# PCA_0005_FULL_CB_Power_REV_B.net
KiCad netlist of a schematic drawn in Altium Designer
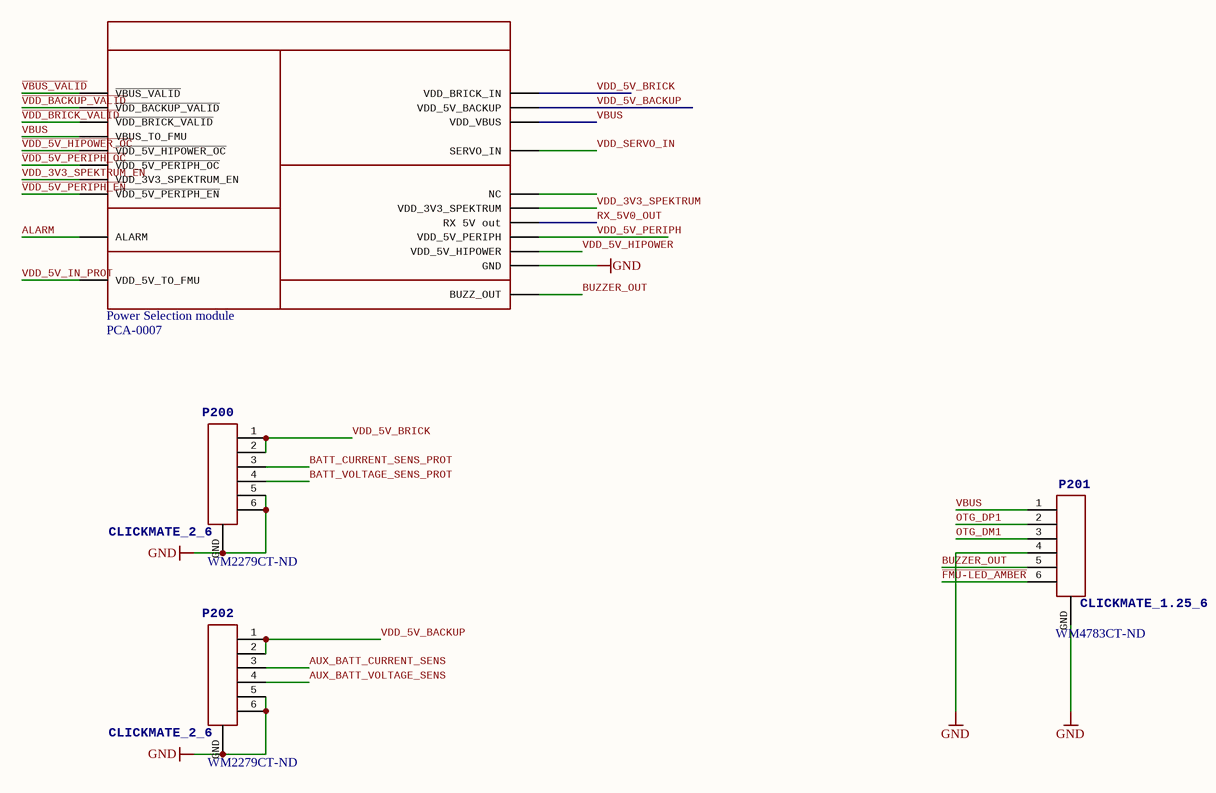
[diagram p0: PCA_0005_FULL_CB_Power_REV_B.SchDoc]

(export (version "E")
  (design (tool "Eeschema 10.0.6"))
  (components
    (comp (ref "P200")
      (value "CLICKMATE_2_6")
      (footprint "CLICKMATE_V6_2MM")
      (description "Connector, Header, 6Pos, 2.54MM, Vert, THT, Au")
      (fields (field (name "SUPPLIER PART NUMBER 1") "WM2279CT-ND") (field (name "3DR_PARTNO") "PRT0445"))
      (libsource (lib "PCA_0005_FULL_CB_REV_A") (part "CLICKMATE_2_6"))
    )
    (comp (ref "P201")
      (value "CLICKMATE_1.25_6")
      (footprint "CLICKMATE_V6")
      (description "Connector, Rcpt, 6Pos, 1.25MM, W/B, VERT, SMD, Tin")
      (fields (field (name "SUPPLIER PART NUMBER 1") "WM4783CT-ND") (field (name "3DR_PARTNO") "PRT0439"))
      (libsource (lib "PCA_0005_FULL_CB_REV_A") (part "CLICKMATE_1.25_6"))
    )
    (comp (ref "P202")
      (value "CLICKMATE_2_6")
      (footprint "CLICKMATE_V6_2MM")
      (description "Connector, Header, 6Pos, 2.54MM, Vert, THT, Au")
      (fields (field (name "SUPPLIER PART NUMBER 1") "WM2279CT-ND") (field (name "3DR_PARTNO") "PRT0445"))
      (libsource (lib "PCA_0005_FULL_CB_REV_A") (part "CLICKMATE_2_6"))
    )
    (comp (ref "PSM200")
      (value "Power Selection module")
      (footprint "PSM")
      (description "PCA, PSM, PX4, Assembly")
      (fields (field (name "SUPPLIER PART NUMBER 1") "PCA-0007") (field (name "3DR_PARTNO") "PCA0007"))
      (libsource (lib "PCA_0005_FULL_CB_REV_A") (part "PSMPSM"))
    )
  )
  (nets
    (net (code "1") (name "/ALARM") (class "Default")
      (node (ref "PSM200") (pin "ALARM") (pinfunction "ALARM_ALARM") (pintype "passive"))
    )
    (net (code "2") (name "/AUX_BATT_CURRENT_SENS") (class "Default")
      (node (ref "P202") (pin "3") (pinfunction "3_3") (pintype "passive"))
    )
    (net (code "3") (name "/AUX_BATT_VOLTAGE_SENS") (class "Default")
      (node (ref "P202") (pin "4") (pinfunction "4_4") (pintype "passive"))
    )
    (net (code "4") (name "/BATT_CURRENT_SENS_PROT") (class "Default")
      (node (ref "P200") (pin "3") (pinfunction "3_3") (pintype "passive"))
    )
    (net (code "5") (name "/BATT_VOLTAGE_SENS_PROT") (class "Default")
      (node (ref "P200") (pin "4") (pinfunction "4_4") (pintype "passive"))
    )
    (net (code "6") (name "/BUZZER_OUT") (class "Default")
      (node (ref "P201") (pin "5") (pinfunction "5_5") (pintype "passive"))
      (node (ref "PSM200") (pin "BUZZER_OUT") (pinfunction "BUZZ_OUT_BUZZER_OUT") (pintype "passive"))
    )
    (net (code "7") (name "/OTG_DM1") (class "Default")
      (node (ref "P201") (pin "3") (pinfunction "3_3") (pintype "passive"))
    )
    (net (code "8") (name "/OTG_DP1") (class "Default")
      (node (ref "P201") (pin "2") (pinfunction "2_2") (pintype "passive"))
    )
    (net (code "9") (name "/RX_5V0_OUT") (class "Default")
      (node (ref "PSM200") (pin "RX") (pinfunction "RX_5V_out_RX") (pintype "passive"))
    )
    (net (code "10") (name "/VBUS") (class "Default")
      (node (ref "P201") (pin "1") (pinfunction "1_1") (pintype "passive"))
      (node (ref "PSM200") (pin "VBUS") (pinfunction "VBUS_TO_FMU_VBUS") (pintype "passive"))
      (node (ref "PSM200") (pin "VDD_VBUS") (pinfunction "VDD_VBUS_VDD_VBUS") (pintype "passive"))
    )
    (net (code "11") (name "/VDD_3V3_SPEKTRUM") (class "Default")
      (node (ref "PSM200") (pin "SPEK") (pinfunction "VDD_3V3_SPEKTRUM_SPEK") (pintype "passive"))
    )
    (net (code "12") (name "/VDD_3V3_SPEKTRUM_EN") (class "Default")
      (node (ref "PSM200") (pin "VDD_3V3_SPEKTRUM_EN") (pinfunction "VDD_3V3_SPEKTRUM_EN_VDD_3V3_SPEKTRUM_EN") (pintype "passive"))
    )
    (net (code "13") (name "/VDD_5V_BACKUP") (class "Default")
      (node (ref "P202") (pin "1") (pinfunction "1_1") (pintype "passive"))
      (node (ref "P202") (pin "2") (pinfunction "2_2") (pintype "passive"))
      (node (ref "PSM200") (pin "VDD_5V_BACKUP") (pinfunction "VDD_5V_BACKUP_VDD_5V_BACKUP") (pintype "passive"))
    )
    (net (code "14") (name "/VDD_5V_BRICK") (class "Default")
      (node (ref "P200") (pin "1") (pinfunction "1_1") (pintype "passive"))
      (node (ref "P200") (pin "2") (pinfunction "2_2") (pintype "passive"))
      (node (ref "PSM200") (pin "VDD_BRICK_IN") (pinfunction "VDD_BRICK_IN_VDD_BRICK_IN") (pintype "passive"))
    )
    (net (code "15") (name "/VDD_5V_HIPOWER") (class "Default")
      (node (ref "PSM200") (pin "5V_HIPOWER") (pinfunction "VDD_5V_HIPOWER_5V_HIPOWER") (pintype "passive"))
    )
    (net (code "16") (name "/VDD_5V_IN_PROT") (class "Default")
      (node (ref "PSM200") (pin "VDD_5V_IN_PROT") (pinfunction "VDD_5V_TO_FMU_VDD_5V_IN_PROT") (pintype "passive"))
    )
    (net (code "17") (name "/VDD_5V_PERIPH") (class "Default")
      (node (ref "PSM200") (pin "5V_PERIPH") (pinfunction "VDD_5V_PERIPH_5V_PERIPH") (pintype "passive"))
    )
    (net (code "18") (name "/VDD_SERVO_IN") (class "Default")
      (node (ref "PSM200") (pin "SERVO_IN") (pinfunction "SERVO_IN_SERVO_IN") (pintype "passive"))
    )
    (net (code "19") (name "/~{FMU-LED_AMBER}") (class "Default")
      (node (ref "P201") (pin "6") (pinfunction "6_6") (pintype "passive"))
    )
    (net (code "20") (name "/~{VBUS_VALID}") (class "Default")
      (node (ref "PSM200") (pin "!VBUS_VALID") (pinfunction "~{VBUS_VALID}_!VBUS_VALID") (pintype "passive"))
    )
    (net (code "21") (name "/~{VDD_5V_HIPOWER_OC}") (class "Default")
      (node (ref "PSM200") (pin "!VDD_5V_HIPOWER_OC") (pinfunction "~{VDD_5V_HIPOWER_OC}_!VDD_5V_HIPOWER_OC") (pintype "passive"))
    )
    (net (code "22") (name "/~{VDD_5V_PERIPH_EN}") (class "Default")
      (node (ref "PSM200") (pin "!VDD_5V_PERIPH_EN") (pinfunction "~{VDD_5V_PERIPH_EN}_!VDD_5V_PERIPH_EN") (pintype "passive"))
    )
    (net (code "23") (name "/~{VDD_5V_PERIPH_OC}") (class "Default")
      (node (ref "PSM200") (pin "!VDD_5V_PERIPH_OC") (pinfunction "~{VDD_5V_PERIPH_OC}_!VDD_5V_PERIPH_OC") (pintype "passive"))
    )
    (net (code "24") (name "/~{VDD_BACKUP_VALID}") (class "Default")
      (node (ref "PSM200") (pin "!VDD_BACKUP_VALID") (pinfunction "~{VDD_BACKUP_VALID}_!VDD_BACKUP_VALID") (pintype "passive"))
    )
    (net (code "25") (name "/~{VDD_BRICK_VALID}") (class "Default")
      (node (ref "PSM200") (pin "!VDD_BRICK_VALID") (pinfunction "~{VDD_BRICK_VALID}_!VDD_BRICK_VALID") (pintype "passive"))
    )
    (net (code "26") (name "GND") (class "Default")
      (node (ref "P200") (pin "5") (pinfunction "5_5") (pintype "passive"))
      (node (ref "P200") (pin "6") (pinfunction "6_6") (pintype "passive"))
      (node (ref "P200") (pin "GND") (pinfunction "GND_GND") (pintype "passive"))
      (node (ref "P201") (pin "4") (pinfunction "4_4") (pintype "passive"))
      (node (ref "P201") (pin "GND") (pinfunction "GND_GND") (pintype "passive"))
      (node (ref "P202") (pin "5") (pinfunction "5_5") (pintype "passive"))
      (node (ref "P202") (pin "6") (pinfunction "6_6") (pintype "passive"))
      (node (ref "P202") (pin "GND") (pinfunction "GND_GND") (pintype "passive"))
      (node (ref "PSM200") (pin "GND") (pinfunction "GND_GND") (pintype "passive"))
    )
    (net (code "27") (name "unconnected-(PSM200-PadNC)") (class "Default")
      (node (ref "PSM200") (pin "NC") (pinfunction "NC_NC") (pintype "passive"))
    )
  )
)
